# schematic.net
KiCad netlist of a schematic drawn in EAGLE
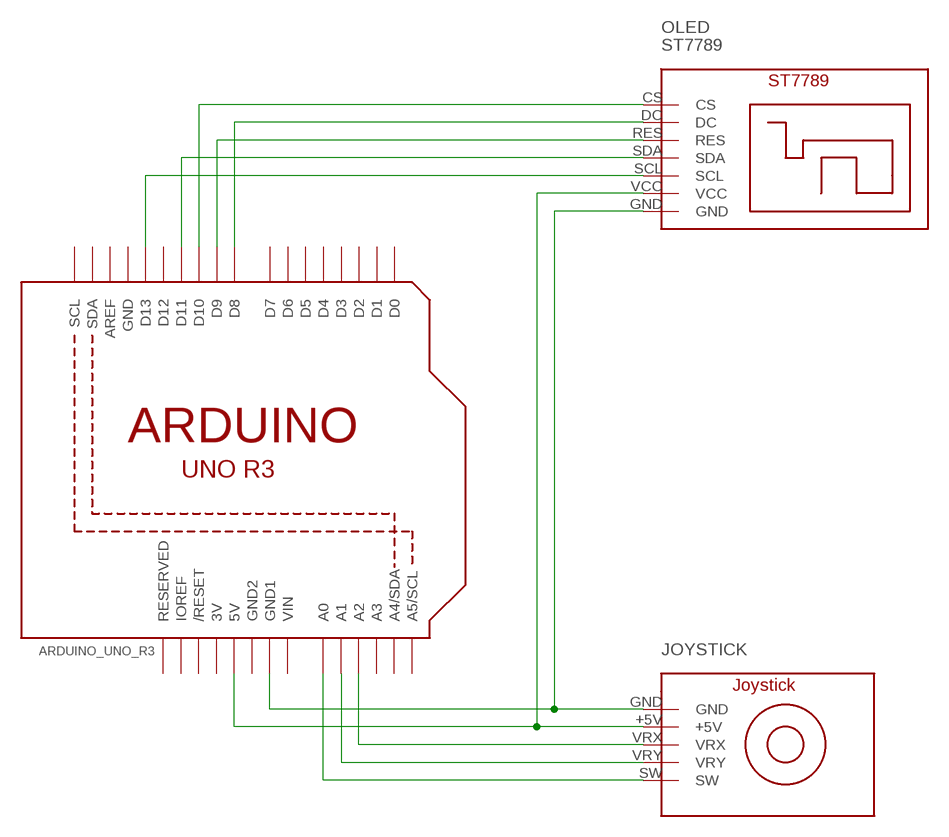
[diagram p0: schematic, sheet 1]

(export (version "E")
  (design (tool "Eeschema 10.0.6"))
  (components
    (comp (ref "ARDUINO_UNO_R3")
      (value "ARDUINOR3-BPLACE")
      (footprint "eagle-import:ARDUINOR3-BPLACE")
      (libsource (lib "eagle-import") (part "ARDUINOR3-BPLACE"))
    )
    (comp (ref "JOYSTICK")
      (value "JOYSTICK")
      (footprint "eagle-import:FP_JOYSTICK")
      (libsource (lib "eagle-import") (part "JOYSTICK"))
    )
    (comp (ref "U$1")
      (value "ST7789")
      (footprint "eagle-import:FP_ST7789")
      (libsource (lib "eagle-import") (part "ST7789"))
    )
  )
  (nets
    (net (code "1") (name "/3V") (class "Default")
      (node (ref "ARDUINO_UNO_R3") (pin "3V") (pinfunction "3V_3V") (pintype "power_in"))
    )
    (net (code "2") (name "/GND") (class "Default")
      (node (ref "ARDUINO_UNO_R3") (pin "GND") (pinfunction "GND_GND") (pintype "power_in"))
    )
    (net (code "3") (name "/GND2") (class "Default")
      (node (ref "ARDUINO_UNO_R3") (pin "GND2") (pinfunction "GND2_GND2") (pintype "power_in"))
    )
    (net (code "4") (name "/VIN") (class "Default")
      (node (ref "ARDUINO_UNO_R3") (pin "VIN") (pinfunction "VIN_VIN") (pintype "power_in"))
    )
    (net (code "5") (name "Net-(ARDUINO_UNO_R3-Pad5V)") (class "Default")
      (node (ref "ARDUINO_UNO_R3") (pin "5V") (pinfunction "5V_5V") (pintype "power_in"))
      (node (ref "JOYSTICK") (pin "+5V") (pinfunction "+5V_+5V") (pintype "bidirectional"))
      (node (ref "U$1") (pin "VCC") (pinfunction "VCC_VCC") (pintype "bidirectional"))
    )
    (net (code "6") (name "Net-(ARDUINO_UNO_R3-PadA0)") (class "Default")
      (node (ref "ARDUINO_UNO_R3") (pin "A0") (pinfunction "A0_A0") (pintype "bidirectional"))
      (node (ref "JOYSTICK") (pin "SW") (pinfunction "SW_SW") (pintype "bidirectional"))
    )
    (net (code "7") (name "Net-(ARDUINO_UNO_R3-PadA1)") (class "Default")
      (node (ref "ARDUINO_UNO_R3") (pin "A1") (pinfunction "A1_A1") (pintype "bidirectional"))
      (node (ref "JOYSTICK") (pin "VRY") (pinfunction "VRY_VRY") (pintype "bidirectional"))
    )
    (net (code "8") (name "Net-(ARDUINO_UNO_R3-PadA2)") (class "Default")
      (node (ref "ARDUINO_UNO_R3") (pin "A2") (pinfunction "A2_A2") (pintype "bidirectional"))
      (node (ref "JOYSTICK") (pin "VRX") (pinfunction "VRX_VRX") (pintype "bidirectional"))
    )
    (net (code "9") (name "Net-(ARDUINO_UNO_R3-PadD8)") (class "Default")
      (node (ref "ARDUINO_UNO_R3") (pin "D8") (pinfunction "D8_D8") (pintype "bidirectional"))
      (node (ref "U$1") (pin "DC") (pinfunction "DC_DC") (pintype "bidirectional"))
    )
    (net (code "10") (name "Net-(ARDUINO_UNO_R3-PadD9)") (class "Default")
      (node (ref "ARDUINO_UNO_R3") (pin "D9") (pinfunction "D9_D9") (pintype "bidirectional"))
      (node (ref "U$1") (pin "RES") (pinfunction "RES_RES") (pintype "bidirectional"))
    )
    (net (code "11") (name "Net-(ARDUINO_UNO_R3-PadD10)") (class "Default")
      (node (ref "ARDUINO_UNO_R3") (pin "D10") (pinfunction "D10_D10") (pintype "bidirectional"))
      (node (ref "U$1") (pin "CS") (pinfunction "CS_CS") (pintype "bidirectional"))
    )
    (net (code "12") (name "Net-(ARDUINO_UNO_R3-PadD11)") (class "Default")
      (node (ref "ARDUINO_UNO_R3") (pin "D11") (pinfunction "D11_D11") (pintype "bidirectional"))
      (node (ref "U$1") (pin "SDA") (pinfunction "SDA_SDA") (pintype "bidirectional"))
    )
    (net (code "13") (name "Net-(ARDUINO_UNO_R3-PadD13)") (class "Default")
      (node (ref "ARDUINO_UNO_R3") (pin "D13") (pinfunction "D13_D13") (pintype "bidirectional"))
      (node (ref "U$1") (pin "SCL") (pinfunction "SCL_SCL") (pintype "bidirectional"))
    )
    (net (code "14") (name "Net-(ARDUINO_UNO_R3-PadGND1)") (class "Default")
      (node (ref "ARDUINO_UNO_R3") (pin "GND1") (pinfunction "GND1_GND1") (pintype "power_in"))
      (node (ref "JOYSTICK") (pin "GND") (pinfunction "GND_GND") (pintype "bidirectional"))
      (node (ref "U$1") (pin "GND") (pinfunction "GND_GND") (pintype "bidirectional"))
    )
    (net (code "15") (name "unconnected-(ARDUINO_UNO_R3-A4{slash}SDA-PadA4)") (class "Default")
      (node (ref "ARDUINO_UNO_R3") (pin "A4") (pinfunction "A4/SDA_A4") (pintype "bidirectional"))
    )
    (net (code "16") (name "unconnected-(ARDUINO_UNO_R3-A5{slash}SCL-PadA5)") (class "Default")
      (node (ref "ARDUINO_UNO_R3") (pin "A5") (pinfunction "A5/SCL_A5") (pintype "bidirectional"))
    )
    (net (code "17") (name "unconnected-(ARDUINO_UNO_R3-PadA3)") (class "Default")
      (node (ref "ARDUINO_UNO_R3") (pin "A3") (pinfunction "A3_A3") (pintype "bidirectional"))
    )
    (net (code "18") (name "unconnected-(ARDUINO_UNO_R3-PadAREF)") (class "Default")
      (node (ref "ARDUINO_UNO_R3") (pin "AREF") (pinfunction "AREF_AREF") (pintype "bidirectional"))
    )
    (net (code "19") (name "unconnected-(ARDUINO_UNO_R3-PadD0)") (class "Default")
      (node (ref "ARDUINO_UNO_R3") (pin "D0") (pinfunction "D0_D0") (pintype "bidirectional"))
    )
    (net (code "20") (name "unconnected-(ARDUINO_UNO_R3-PadD1)") (class "Default")
      (node (ref "ARDUINO_UNO_R3") (pin "D1") (pinfunction "D1_D1") (pintype "bidirectional"))
    )
    (net (code "21") (name "unconnected-(ARDUINO_UNO_R3-PadD2)") (class "Default")
      (node (ref "ARDUINO_UNO_R3") (pin "D2") (pinfunction "D2_D2") (pintype "bidirectional"))
    )
    (net (code "22") (name "unconnected-(ARDUINO_UNO_R3-PadD3)") (class "Default")
      (node (ref "ARDUINO_UNO_R3") (pin "D3") (pinfunction "D3_D3") (pintype "bidirectional"))
    )
    (net (code "23") (name "unconnected-(ARDUINO_UNO_R3-PadD4)") (class "Default")
      (node (ref "ARDUINO_UNO_R3") (pin "D4") (pinfunction "D4_D4") (pintype "bidirectional"))
    )
    (net (code "24") (name "unconnected-(ARDUINO_UNO_R3-PadD5)") (class "Default")
      (node (ref "ARDUINO_UNO_R3") (pin "D5") (pinfunction "D5_D5") (pintype "bidirectional"))
    )
    (net (code "25") (name "unconnected-(ARDUINO_UNO_R3-PadD6)") (class "Default")
      (node (ref "ARDUINO_UNO_R3") (pin "D6") (pinfunction "D6_D6") (pintype "bidirectional"))
    )
    (net (code "26") (name "unconnected-(ARDUINO_UNO_R3-PadD7)") (class "Default")
      (node (ref "ARDUINO_UNO_R3") (pin "D7") (pinfunction "D7_D7") (pintype "bidirectional"))
    )
    (net (code "27") (name "unconnected-(ARDUINO_UNO_R3-PadD12)") (class "Default")
      (node (ref "ARDUINO_UNO_R3") (pin "D12") (pinfunction "D12_D12") (pintype "bidirectional"))
    )
    (net (code "28") (name "unconnected-(ARDUINO_UNO_R3-PadIOREF)") (class "Default")
      (node (ref "ARDUINO_UNO_R3") (pin "IOREF") (pinfunction "IOREF_IOREF") (pintype "output"))
    )
    (net (code "29") (name "unconnected-(ARDUINO_UNO_R3-PadRESERVED)") (class "Default")
      (node (ref "ARDUINO_UNO_R3") (pin "RESERVED") (pinfunction "RESERVED_RESERVED") (pintype "no_connect"))
    )
    (net (code "30") (name "unconnected-(ARDUINO_UNO_R3-PadSCL)") (class "Default")
      (node (ref "ARDUINO_UNO_R3") (pin "SCL") (pinfunction "SCL_SCL") (pintype "bidirectional"))
    )
    (net (code "31") (name "unconnected-(ARDUINO_UNO_R3-PadSDA)") (class "Default")
      (node (ref "ARDUINO_UNO_R3") (pin "SDA") (pinfunction "SDA_SDA") (pintype "bidirectional"))
    )
    (net (code "32") (name "unconnected-(ARDUINO_UNO_R3-{slash}RESET-PadRESET)") (class "Default")
      (node (ref "ARDUINO_UNO_R3") (pin "RESET") (pinfunction "/RESET_RESET") (pintype "bidirectional"))
    )
  )
)
